# SPARC_Gamma_LED_PCB.net
KiCad netlist of a schematic drawn in EAGLE
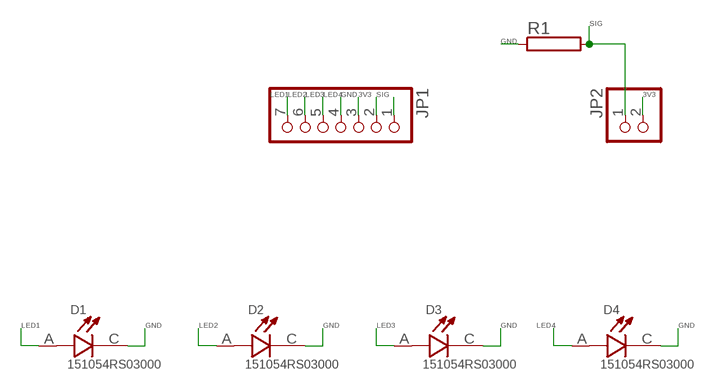
[diagram p0: schematic, sheet 1]

(export (version "E")
  (design (tool "Eeschema 10.0.6"))
  (components
    (comp (ref "D1")
      (value "151054RS03000")
      (footprint "eagle-import:LED_151054RS03000")
      (fields (field (name "MF") "Würth Elektronik"))
      (libsource (lib "eagle-import") (part "151054RS03000"))
    )
    (comp (ref "D2")
      (value "151054RS03000")
      (footprint "eagle-import:LED_151054RS03000")
      (fields (field (name "MF") "Würth Elektronik"))
      (libsource (lib "eagle-import") (part "151054RS03000"))
    )
    (comp (ref "D3")
      (value "151054RS03000")
      (footprint "eagle-import:LED_151054RS03000")
      (fields (field (name "MF") "Würth Elektronik"))
      (libsource (lib "eagle-import") (part "151054RS03000"))
    )
    (comp (ref "D4")
      (value "151054RS03000")
      (footprint "eagle-import:LED_151054RS03000")
      (fields (field (name "MF") "Würth Elektronik"))
      (libsource (lib "eagle-import") (part "151054RS03000"))
    )
    (comp (ref "JP1")
      (value "PINHD-1X7")
      (footprint "eagle-import:1X07")
      (libsource (lib "eagle-import") (part "PINHD-1X7"))
    )
    (comp (ref "JP2")
      (value "PINHD-1X2")
      (footprint "eagle-import:1X02")
      (libsource (lib "eagle-import") (part "PINHD-1X2"))
    )
    (comp (ref "R1")
      (value "RAC01")
      (footprint "eagle-import:AC01")
      (libsource (lib "eagle-import") (part "RAC01"))
    )
  )
  (nets
    (net (code "1") (name "/3V3") (class "Default")
      (node (ref "JP1") (pin "2") (pinfunction "2_2") (pintype "passive"))
      (node (ref "JP2") (pin "2") (pinfunction "2_2") (pintype "passive"))
    )
    (net (code "2") (name "/GND") (class "Default")
      (node (ref "D1") (pin "C") (pinfunction "C_C") (pintype "passive"))
      (node (ref "D2") (pin "C") (pinfunction "C_C") (pintype "passive"))
      (node (ref "D3") (pin "C") (pinfunction "C_C") (pintype "passive"))
      (node (ref "D4") (pin "C") (pinfunction "C_C") (pintype "passive"))
      (node (ref "JP1") (pin "3") (pinfunction "3_3") (pintype "passive"))
      (node (ref "R1") (pin "1") (pinfunction "1_1") (pintype "passive"))
    )
    (net (code "3") (name "/LED1") (class "Default")
      (node (ref "D1") (pin "A") (pinfunction "A_A") (pintype "passive"))
      (node (ref "JP1") (pin "7") (pinfunction "7_7") (pintype "passive"))
    )
    (net (code "4") (name "/LED2") (class "Default")
      (node (ref "D2") (pin "A") (pinfunction "A_A") (pintype "passive"))
      (node (ref "JP1") (pin "6") (pinfunction "6_6") (pintype "passive"))
    )
    (net (code "5") (name "/LED3") (class "Default")
      (node (ref "D3") (pin "A") (pinfunction "A_A") (pintype "passive"))
      (node (ref "JP1") (pin "5") (pinfunction "5_5") (pintype "passive"))
    )
    (net (code "6") (name "/LED4") (class "Default")
      (node (ref "D4") (pin "A") (pinfunction "A_A") (pintype "passive"))
      (node (ref "JP1") (pin "4") (pinfunction "4_4") (pintype "passive"))
    )
    (net (code "7") (name "/SIG") (class "Default")
      (node (ref "JP1") (pin "1") (pinfunction "1_1") (pintype "passive"))
      (node (ref "JP2") (pin "1") (pinfunction "1_1") (pintype "passive"))
      (node (ref "R1") (pin "2") (pinfunction "2_2") (pintype "passive"))
    )
  )
)
